# Sheet2-power.net
KiCad netlist of a schematic drawn in Altium Designer
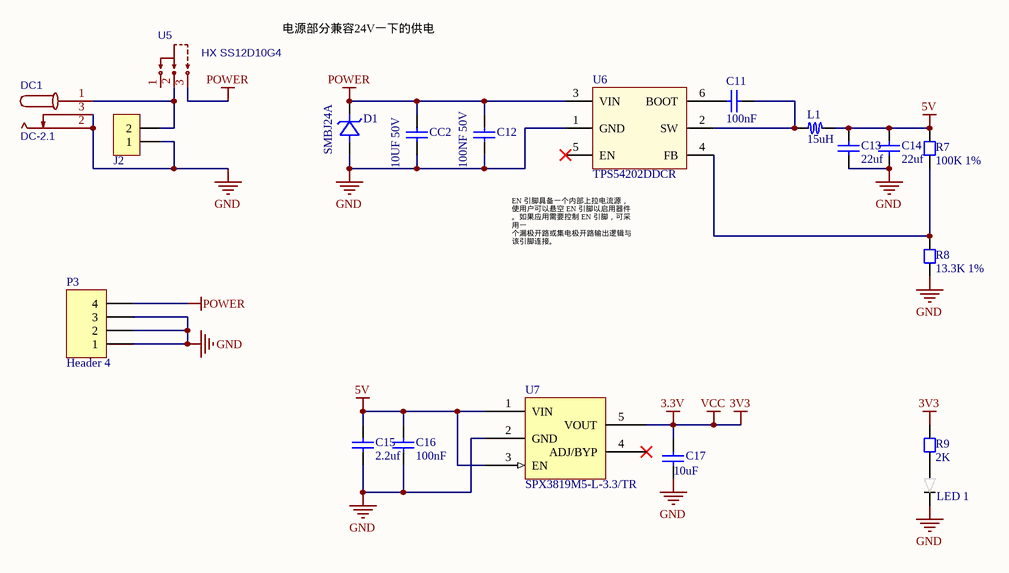
[diagram p0: Sheet2-power.SchDoc]

(export (version "E")
  (design (tool "Eeschema 10.0.6"))
  (components
    (comp (ref "C11")
      (value "100nF")
      (footprint "CC1608-0603")
      (description "0603封装的电容")
      (fields (field (name "PUBLISHER") "Altium Limited"))
      (libsource (lib "base") (part "Cap Chip 0603"))
    )
    (comp (ref "C12")
      (value "100NF 50V")
      (footprint "CC1608-0603")
      (description "0603封装的电容")
      (fields (field (name "PUBLISHER") "Altium Limited"))
      (libsource (lib "base") (part "Cap Chip 0603"))
    )
    (comp (ref "C13")
      (value "22uf")
      (footprint "CC1608-0603")
      (description "0603封装的电容")
      (fields (field (name "PUBLISHER") "Altium Limited"))
      (libsource (lib "base") (part "Cap Chip 0603"))
    )
    (comp (ref "C14")
      (value "22uf")
      (footprint "CC1608-0603")
      (description "0603封装的电容")
      (fields (field (name "PUBLISHER") "Altium Limited"))
      (libsource (lib "base") (part "Cap Chip 0603"))
    )
    (comp (ref "C15")
      (value "2.2uf")
      (footprint "CC1608-0603")
      (description "0603封装的电容")
      (fields (field (name "PUBLISHER") "Altium Limited"))
      (libsource (lib "base") (part "Cap Chip 0603"))
    )
    (comp (ref "C16")
      (value "100nF")
      (footprint "CC1608-0603")
      (description "0603封装的电容")
      (fields (field (name "PUBLISHER") "Altium Limited"))
      (libsource (lib "base") (part "Cap Chip 0603"))
    )
    (comp (ref "C17")
      (value "10uF")
      (footprint "CC1608-0603")
      (description "贴片电容")
      (libsource (lib "tianxiaohua_Schlib") (part "Chip capacitor"))
    )
    (comp (ref "CC2")
      (value "10UF 50V")
      (footprint "CC3216-1206")
      (description "Polarized Capacitor (Radial)")
      (fields (field (name "Comment") "Cap Chip 1206") (field (name "PUBLISHER") "Altium Limited"))
      (libsource (lib "base") (part "Cap Chip 1206"))
    )
    (comp (ref "D1")
      (value "SMBJ24A")
      (footprint "DO-214 AA")
      (description "TVS稳压二极管")
      (libsource (lib "transistor") (part "SMBJ18A"))
    )
    (comp (ref "DC1")
      (value "DC-2.1")
      (footprint "DC-IN-SMD_DC-050-25A")
      (description "DC贴片插座")
      (fields
        (field (name "BOM_SUPPLIER PART") "C707275")
        (field (name "BOM_MANUFACTURER PART") "DC-050-25A")
        (field (name "CONTRIBUTOR") "LCSC")
      )
      (libsource (lib "Connectors") (part "DC-050"))
    )
    (comp (ref "J2")
      (value "HDR-1X3")
      (footprint "KF301-5.0-2P")
      (description "2P拧螺丝接口")
      (fields (field (name "版权归属") "封装库来自淘宝 ID：黄晶宝石"))
      (libsource (lib "Connectors") (part "KF301 2P"))
    )
    (comp (ref "L1")
      (value "15uH")
      (footprint "Inductor-4018")
      (description "贴片电感 1206封装")
      (libsource (lib "base") (part "Inductor-4018"))
    )
    (comp (ref "LED 1") (value "LED 0603") (footprint "LED 0603") (libsource (lib "base") (part "LED 0603")))
    (comp (ref "P3")
      (value "Header 4")
      (footprint "HDR1X4")
      (description "Header, 4-Pin")
      (fields (field (name "PUBLISHER") "Altium Limited"))
      (libsource (lib "Connectors") (part "Header 4"))
    )
    (comp (ref "R7")
      (value "100K 1%")
      (footprint "CR1608-0603")
      (description "0603封装电阻")
      (fields (field (name "PUBLISHER") "Altium Limited"))
      (libsource (lib "base") (part "Resistor Chip 0603"))
    )
    (comp (ref "R8")
      (value "13.3K 1%")
      (footprint "CR1608-0603")
      (description "0603封装电阻")
      (fields (field (name "PUBLISHER") "Altium Limited"))
      (libsource (lib "base") (part "Resistor Chip 0603"))
    )
    (comp (ref "R9")
      (value "2K")
      (footprint "CR1608-0603")
      (description "0603封装电阻")
      (fields (field (name "PUBLISHER") "Altium Limited"))
      (libsource (lib "") (part "Resistor Chip 0603_1"))
    )
    (comp (ref "U5")
      (value "HX SS12D10G4")
      (footprint "SS12D10-G4")
      (fields (field (name "BOM_SUPPLIER PART") "C5149841") (field (name "CONTRIBUTOR") "lcsc"))
      (libsource (lib "Connectors") (part "SS12D10G4"))
    )
    (comp (ref "U6")
      (value "TPS54202DDCR")
      (footprint "SOT23-6")
      (description "同步降压转换器芯片 500Khz 4.2~28V输入，2A输出")
      (libsource (lib "power-chip") (part "TPS54202DDCR"))
    )
    (comp (ref "U7")
      (value "SPX3819M5-L-3.3/TR")
      (footprint "SOT23-5")
      (description "LDO 3.3V , SOT-23-5 500ma")
      (libsource (lib "power-chip") (part "SPX3819M5-L-3.3/TR"))
    )
  )
  (nets
    (net (code "1") (name "3.3V") (class "Default")
      (node (ref "C17") (pin "1") (pinfunction "1_1") (pintype "passive"))
      (node (ref "R9") (pin "1") (pinfunction "1_1") (pintype "passive"))
      (node (ref "U7") (pin "5") (pinfunction "VOUT_5") (pintype "passive"))
    )
    (net (code "2") (name "5V") (class "Default")
      (node (ref "C13") (pin "2") (pinfunction "2_2") (pintype "passive"))
      (node (ref "C14") (pin "2") (pinfunction "2_2") (pintype "passive"))
      (node (ref "C15") (pin "2") (pinfunction "2_2") (pintype "passive"))
      (node (ref "C16") (pin "2") (pinfunction "2_2") (pintype "passive"))
      (node (ref "L1") (pin "2") (pinfunction "2_2") (pintype "passive"))
      (node (ref "R7") (pin "2") (pinfunction "2_2") (pintype "passive"))
      (node (ref "U7") (pin "1") (pinfunction "VIN_1") (pintype "power_in"))
      (node (ref "U7") (pin "3") (pinfunction "EN_3") (pintype "input"))
    )
    (net (code "3") (name "GND") (class "Default")
      (node (ref "C12") (pin "1") (pinfunction "1_1") (pintype "passive"))
      (node (ref "C13") (pin "1") (pinfunction "1_1") (pintype "passive"))
      (node (ref "C14") (pin "1") (pinfunction "1_1") (pintype "passive"))
      (node (ref "C15") (pin "1") (pinfunction "1_1") (pintype "passive"))
      (node (ref "C16") (pin "1") (pinfunction "1_1") (pintype "passive"))
      (node (ref "C17") (pin "2") (pinfunction "2_2") (pintype "passive"))
      (node (ref "CC2") (pin "1") (pinfunction "1_1") (pintype "passive"))
      (node (ref "D1") (pin "2") (pinfunction "A_2") (pintype "passive"))
      (node (ref "DC1") (pin "2") (pinfunction "2_2") (pintype "passive"))
      (node (ref "DC1") (pin "3") (pinfunction "3_3") (pintype "passive"))
      (node (ref "J2") (pin "1") (pinfunction "1_1") (pintype "passive"))
      (node (ref "LED 1") (pin "2") (pinfunction "2_2") (pintype "passive"))
      (node (ref "P3") (pin "1") (pinfunction "1_1") (pintype "passive"))
      (node (ref "P3") (pin "2") (pinfunction "2_2") (pintype "passive"))
      (node (ref "P3") (pin "3") (pinfunction "3_3") (pintype "passive"))
      (node (ref "R8") (pin "1") (pinfunction "1_1") (pintype "passive"))
      (node (ref "U6") (pin "1") (pinfunction "GND_1") (pintype "passive"))
      (node (ref "U7") (pin "2") (pinfunction "GND_2") (pintype "power_in"))
    )
    (net (code "4") (name "Net-(DC1-Pad1)") (class "Default")
      (node (ref "DC1") (pin "1") (pinfunction "1_1") (pintype "passive"))
      (node (ref "J2") (pin "2") (pinfunction "2_2") (pintype "passive"))
      (node (ref "U5") (pin "2") (pinfunction "2_2") (pintype "passive"))
    )
    (net (code "5") (name "Net-(LED 1-Pad1)") (class "Default")
      (node (ref "LED 1") (pin "1") (pinfunction "1_1") (pintype "passive"))
      (node (ref "R9") (pin "2") (pinfunction "2_2") (pintype "passive"))
    )
    (net (code "6") (name "Net-(U6-BOOT)") (class "Default")
      (node (ref "C11") (pin "1") (pinfunction "1_1") (pintype "passive"))
      (node (ref "U6") (pin "6") (pinfunction "BOOT_6") (pintype "passive"))
    )
    (net (code "7") (name "Net-(U6-FB)") (class "Default")
      (node (ref "R7") (pin "1") (pinfunction "1_1") (pintype "passive"))
      (node (ref "R8") (pin "2") (pinfunction "2_2") (pintype "passive"))
      (node (ref "U6") (pin "4") (pinfunction "FB_4") (pintype "passive"))
    )
    (net (code "8") (name "Net-(U6-SW)") (class "Default")
      (node (ref "C11") (pin "2") (pinfunction "2_2") (pintype "passive"))
      (node (ref "L1") (pin "1") (pinfunction "1_1") (pintype "passive"))
      (node (ref "U6") (pin "2") (pinfunction "SW_2") (pintype "passive"))
    )
    (net (code "9") (name "POWER") (class "Default")
      (node (ref "C12") (pin "2") (pinfunction "2_2") (pintype "passive"))
      (node (ref "CC2") (pin "2") (pinfunction "2_2") (pintype "passive"))
      (node (ref "D1") (pin "1") (pinfunction "K_1") (pintype "passive"))
      (node (ref "P3") (pin "4") (pinfunction "4_4") (pintype "passive"))
      (node (ref "U5") (pin "3") (pinfunction "3_3") (pintype "passive"))
      (node (ref "U6") (pin "3") (pinfunction "VIN_3") (pintype "passive"))
    )
    (net (code "10") (name "unconnected-(U5-Pad1)") (class "Default")
      (node (ref "U5") (pin "1") (pinfunction "1_1") (pintype "passive"))
    )
    (net (code "11") (name "unconnected-(U6-EN-Pad5)") (class "Default")
      (node (ref "U6") (pin "5") (pinfunction "EN_5") (pintype "passive+no_connect"))
    )
    (net (code "12") (name "unconnected-(U7-ADJ{slash}BYP-Pad4)") (class "Default")
      (node (ref "U7") (pin "4") (pinfunction "ADJ/BYP_4") (pintype "passive+no_connect"))
    )
  )
)
